# gdm-multiiface.net
KiCad netlist of a schematic drawn in EAGLE
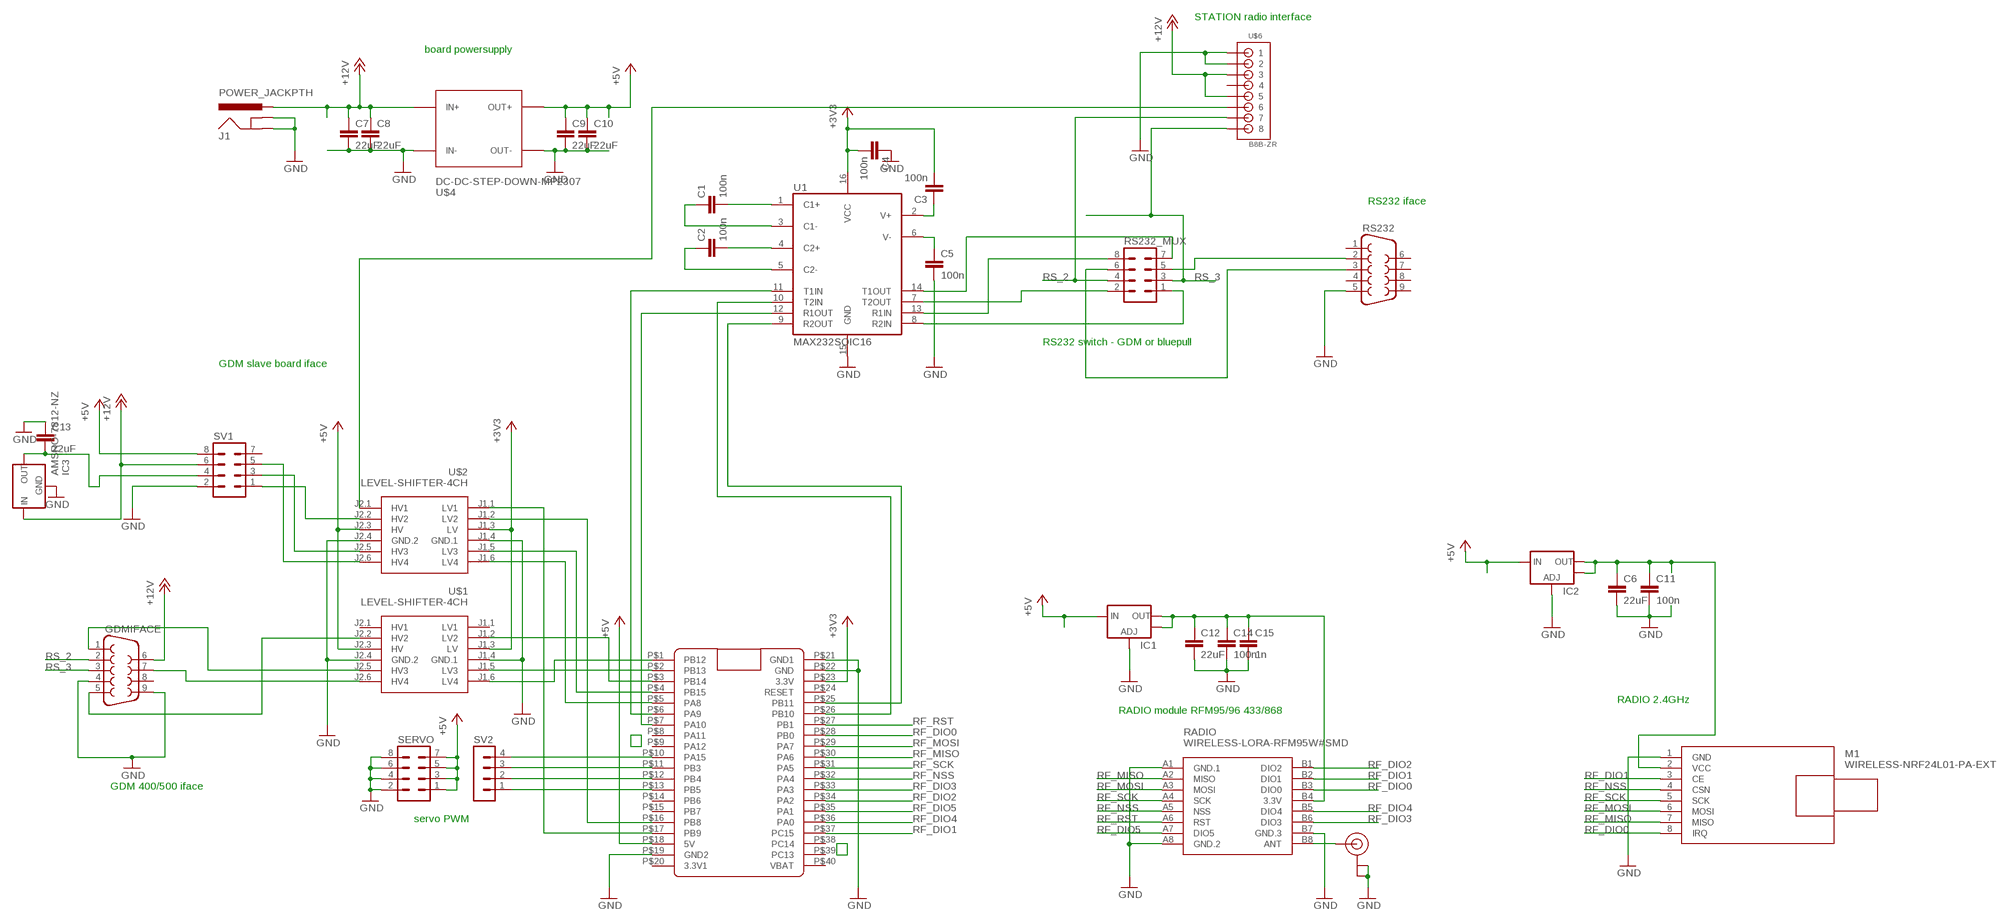
[diagram p0: schematic, sheet 1]

(export (version "E")
  (design (tool "Eeschema 10.0.6"))
  (components
    (comp (ref "BLUEPILL")
      (value "BLUE_PILL")
      (footprint "eagle-import:BLUE_PILL")
      (libsource (lib "eagle-import") (part "BLUE_PILL"))
    )
    (comp (ref "C1")
      (value "100n")
      (footprint "eagle-import:C0805")
      (libsource (lib "eagle-import") (part "C-EUC0805"))
    )
    (comp (ref "C2")
      (value "100n")
      (footprint "eagle-import:C0805")
      (libsource (lib "eagle-import") (part "C-EUC0805"))
    )
    (comp (ref "C3")
      (value "100n")
      (footprint "eagle-import:C0805")
      (libsource (lib "eagle-import") (part "C-EUC0805"))
    )
    (comp (ref "C4")
      (value "100n")
      (footprint "eagle-import:C0805")
      (libsource (lib "eagle-import") (part "C-EUC0805"))
    )
    (comp (ref "C5")
      (value "100n")
      (footprint "eagle-import:C0805")
      (libsource (lib "eagle-import") (part "C-EUC0805"))
    )
    (comp (ref "C6")
      (value "22uF")
      (footprint "eagle-import:C1210K")
      (libsource (lib "eagle-import") (part "C-EUC1210K"))
    )
    (comp (ref "C7")
      (value "22uF")
      (footprint "eagle-import:C1210K")
      (libsource (lib "eagle-import") (part "C-EUC1210K"))
    )
    (comp (ref "C8")
      (value "22uF")
      (footprint "eagle-import:C1210K")
      (libsource (lib "eagle-import") (part "C-EUC1210K"))
    )
    (comp (ref "C9")
      (value "22uF")
      (footprint "eagle-import:C1210K")
      (libsource (lib "eagle-import") (part "C-EUC1210K"))
    )
    (comp (ref "C10")
      (value "22uF")
      (footprint "eagle-import:C1210K")
      (libsource (lib "eagle-import") (part "C-EUC1210K"))
    )
    (comp (ref "C11")
      (value "100n")
      (footprint "eagle-import:C0805K")
      (libsource (lib "eagle-import") (part "C-EUC0805K"))
    )
    (comp (ref "C12")
      (value "22uF")
      (footprint "eagle-import:C1210K")
      (libsource (lib "eagle-import") (part "C-EUC1210K"))
    )
    (comp (ref "C13")
      (value "22uF")
      (footprint "eagle-import:C1210K")
      (libsource (lib "eagle-import") (part "C-EUC1210K"))
    )
    (comp (ref "C14")
      (value "100n")
      (footprint "eagle-import:C0805K")
      (libsource (lib "eagle-import") (part "C-EUC0805K"))
    )
    (comp (ref "C15")
      (value "1n")
      (footprint "eagle-import:C0805K")
      (libsource (lib "eagle-import") (part "C-EUC0805K"))
    )
    (comp (ref "GDMIFACE")
      (value "DB9FEMALE")
      (footprint "eagle-import:DB9")
      (libsource (lib "eagle-import") (part "DB9FEMALE"))
    )
    (comp (ref "IC1")
      (value "V_REG_LM1117SOT223")
      (footprint "eagle-import:SOT223")
      (libsource (lib "eagle-import") (part "V_REG_LM1117SOT223"))
    )
    (comp (ref "IC2")
      (value "V_REG_LM1117SOT223")
      (footprint "eagle-import:SOT223")
      (libsource (lib "eagle-import") (part "V_REG_LM1117SOT223"))
    )
    (comp (ref "IC3")
      (value "AMSRO-7812-NZ")
      (footprint "eagle-import:79XXS")
      (libsource (lib "eagle-import") (part "79XXS"))
    )
    (comp (ref "J1")
      (value "POWER_JACKPTH")
      (footprint "eagle-import:POWER_JACK_PTH")
      (libsource (lib "eagle-import") (part "POWER_JACKPTH"))
    )
    (comp (ref "M1")
      (value "WIRELESS-NRF24L01-PA-EXT")
      (footprint "eagle-import:WIRELESS-NRF24L01-PA-EXT")
      (libsource (lib "eagle-import") (part "WIRELESS-NRF24L01-PA-EXT"))
    )
    (comp (ref "RADIO")
      (value "WIRELESS-LORA-RFM95W#SMD")
      (footprint "eagle-import:WIRELESS-LORA-RFM95W#SMD")
      (libsource (lib "eagle-import") (part "WIRELESS-LORA-RFM95W#SMD"))
    )
    (comp (ref "RS232")
      (value "DB9FEMALE")
      (footprint "eagle-import:DB9")
      (libsource (lib "eagle-import") (part "DB9FEMALE"))
    )
    (comp (ref "RS232_MUX")
      (value "MA04-2")
      (footprint "eagle-import:MA04-2")
      (libsource (lib "eagle-import") (part "MA04-2"))
    )
    (comp (ref "SERVO")
      (value "MA04-2")
      (footprint "eagle-import:MA04-2")
      (libsource (lib "eagle-import") (part "MA04-2"))
    )
    (comp (ref "SV1")
      (value "MA04-2")
      (footprint "eagle-import:MA04-2")
      (libsource (lib "eagle-import") (part "MA04-2"))
    )
    (comp (ref "SV2")
      (value "MA04-1")
      (footprint "eagle-import:MA04-1")
      (libsource (lib "eagle-import") (part "MA04-1"))
    )
    (comp (ref "U$1")
      (value "LEVEL-SHIFTER-4CH")
      (footprint "eagle-import:LEVEL-SHIFTER-4CH")
      (libsource (lib "eagle-import") (part "LEVEL-SHIFTER-4CH"))
    )
    (comp (ref "U$2")
      (value "LEVEL-SHIFTER-4CH")
      (footprint "eagle-import:LEVEL-SHIFTER-4CH")
      (libsource (lib "eagle-import") (part "LEVEL-SHIFTER-4CH"))
    )
    (comp (ref "U$3")
      (value "U.FL")
      (footprint "eagle-import:U.FL")
      (libsource (lib "eagle-import") (part "U.FL"))
    )
    (comp (ref "U$4")
      (value "DC-DC-STEP-DOWN-MP2307")
      (footprint "eagle-import:DC-DC-STEP-DOWN-MP2307")
      (libsource (lib "eagle-import") (part "DC-DC-STEP-DOWN-MP2307"))
    )
    (comp (ref "U$6")
      (value "B8B-ZR")
      (footprint "eagle-import:B8B-ZR")
      (libsource (lib "eagle-import") (part "B8B-ZR"))
    )
    (comp (ref "U1")
      (value "MAX232SOIC16")
      (footprint "eagle-import:SO016")
      (libsource (lib "eagle-import") (part "MAX232SOIC16"))
    )
  )
  (nets
    (net (code "1") (name "+3V3") (class "Default")
      (node (ref "BLUEPILL") (pin "P$23") (pinfunction "3.3V_P$23") (pintype "bidirectional"))
      (node (ref "C3") (pin "2") (pinfunction "2_2") (pintype "passive"))
      (node (ref "C4") (pin "2") (pinfunction "2_2") (pintype "passive"))
      (node (ref "U$1") (pin "J1.3") (pinfunction "LV_J1.3") (pintype "power_in"))
      (node (ref "U$2") (pin "J1.3") (pinfunction "LV_J1.3") (pintype "power_in"))
      (node (ref "U1") (pin "16") (pinfunction "VCC_16") (pintype "bidirectional"))
    )
    (net (code "2") (name "+5V") (class "Default")
      (node (ref "BLUEPILL") (pin "P$18") (pinfunction "5V_P$18") (pintype "bidirectional"))
      (node (ref "C10") (pin "1") (pinfunction "1_1") (pintype "passive"))
      (node (ref "C9") (pin "1") (pinfunction "1_1") (pintype "passive"))
      (node (ref "IC1") (pin "3") (pinfunction "IN_3") (pintype "input"))
      (node (ref "IC2") (pin "3") (pinfunction "IN_3") (pintype "input"))
      (node (ref "SERVO") (pin "1") (pinfunction "1_1") (pintype "passive"))
      (node (ref "SERVO") (pin "3") (pinfunction "3_3") (pintype "passive"))
      (node (ref "SERVO") (pin "5") (pinfunction "5_5") (pintype "passive"))
      (node (ref "SERVO") (pin "7") (pinfunction "7_7") (pintype "passive"))
      (node (ref "SV1") (pin "8") (pinfunction "8_8") (pintype "passive"))
      (node (ref "U$1") (pin "J2.3") (pinfunction "HV_J2.3") (pintype "power_in"))
      (node (ref "U$2") (pin "J2.3") (pinfunction "HV_J2.3") (pintype "power_in"))
      (node (ref "U$4") (pin "OUT+") (pinfunction "OUT+_OUT+") (pintype "bidirectional"))
    )
    (net (code "3") (name "+12V") (class "Default")
      (node (ref "C7") (pin "1") (pinfunction "1_1") (pintype "passive"))
      (node (ref "C8") (pin "1") (pinfunction "1_1") (pintype "passive"))
      (node (ref "GDMIFACE") (pin "6") (pinfunction "6_6") (pintype "passive"))
      (node (ref "IC3") (pin "IN") (pinfunction "IN_IN") (pintype "input"))
      (node (ref "J1") (pin "PWR") (pinfunction "PWR_PWR") (pintype "bidirectional"))
      (node (ref "SV1") (pin "6") (pinfunction "6_6") (pintype "passive"))
      (node (ref "U$4") (pin "IN+") (pinfunction "IN+_IN+") (pintype "bidirectional"))
      (node (ref "U$6") (pin "3") (pinfunction "3_3") (pintype "bidirectional"))
      (node (ref "U$6") (pin "5") (pinfunction "5_5") (pintype "bidirectional"))
    )
    (net (code "4") (name "/RF_DIO0") (class "Default")
      (node (ref "BLUEPILL") (pin "P$28") (pinfunction "PB0_P$28") (pintype "bidirectional"))
      (node (ref "M1") (pin "8") (pinfunction "IRQ_8") (pintype "bidirectional"))
      (node (ref "RADIO") (pin "B3") (pinfunction "DIO0_B3") (pintype "bidirectional"))
    )
    (net (code "5") (name "/RF_DIO1") (class "Default")
      (node (ref "BLUEPILL") (pin "P$37") (pinfunction "PC15_P$37") (pintype "bidirectional"))
      (node (ref "M1") (pin "3") (pinfunction "CE_3") (pintype "bidirectional"))
      (node (ref "RADIO") (pin "B2") (pinfunction "DIO1_B2") (pintype "bidirectional"))
    )
    (net (code "6") (name "/RF_DIO2") (class "Default")
      (node (ref "BLUEPILL") (pin "P$34") (pinfunction "PA2_P$34") (pintype "bidirectional"))
      (node (ref "RADIO") (pin "B1") (pinfunction "DIO2_B1") (pintype "bidirectional"))
    )
    (net (code "7") (name "/RF_DIO3") (class "Default")
      (node (ref "BLUEPILL") (pin "P$33") (pinfunction "PA3_P$33") (pintype "bidirectional"))
      (node (ref "RADIO") (pin "B6") (pinfunction "DIO3_B6") (pintype "bidirectional"))
    )
    (net (code "8") (name "/RF_DIO4") (class "Default")
      (node (ref "BLUEPILL") (pin "P$36") (pinfunction "PA0_P$36") (pintype "bidirectional"))
      (node (ref "RADIO") (pin "B5") (pinfunction "DIO4_B5") (pintype "bidirectional"))
    )
    (net (code "9") (name "/RF_DIO5") (class "Default")
      (node (ref "BLUEPILL") (pin "P$35") (pinfunction "PA1_P$35") (pintype "bidirectional"))
      (node (ref "RADIO") (pin "A7") (pinfunction "DIO5_A7") (pintype "bidirectional"))
    )
    (net (code "10") (name "/RF_MISO") (class "Default")
      (node (ref "BLUEPILL") (pin "P$30") (pinfunction "PA6_P$30") (pintype "bidirectional"))
      (node (ref "M1") (pin "7") (pinfunction "MISO_7") (pintype "bidirectional"))
      (node (ref "RADIO") (pin "A2") (pinfunction "MISO_A2") (pintype "bidirectional"))
    )
    (net (code "11") (name "/RF_MOSI") (class "Default")
      (node (ref "BLUEPILL") (pin "P$29") (pinfunction "PA7_P$29") (pintype "bidirectional"))
      (node (ref "M1") (pin "6") (pinfunction "MOSI_6") (pintype "bidirectional"))
      (node (ref "RADIO") (pin "A3") (pinfunction "MOSI_A3") (pintype "bidirectional"))
    )
    (net (code "12") (name "/RF_NSS") (class "Default")
      (node (ref "BLUEPILL") (pin "P$32") (pinfunction "PA4_P$32") (pintype "bidirectional"))
      (node (ref "M1") (pin "4") (pinfunction "CSN_4") (pintype "bidirectional"))
      (node (ref "RADIO") (pin "A5") (pinfunction "NSS_A5") (pintype "bidirectional"))
    )
    (net (code "13") (name "/RF_RST") (class "Default")
      (node (ref "BLUEPILL") (pin "P$27") (pinfunction "PB1_P$27") (pintype "bidirectional"))
      (node (ref "RADIO") (pin "A6") (pinfunction "RST_A6") (pintype "bidirectional"))
    )
    (net (code "14") (name "/RF_SCK") (class "Default")
      (node (ref "BLUEPILL") (pin "P$31") (pinfunction "PA5_P$31") (pintype "bidirectional"))
      (node (ref "M1") (pin "5") (pinfunction "SCK_5") (pintype "bidirectional"))
      (node (ref "RADIO") (pin "A4") (pinfunction "SCK_A4") (pintype "bidirectional"))
    )
    (net (code "15") (name "/RS_2") (class "Default")
      (node (ref "GDMIFACE") (pin "2") (pinfunction "2_2") (pintype "passive"))
      (node (ref "RS232_MUX") (pin "4") (pinfunction "4_4") (pintype "passive"))
      (node (ref "U$6") (pin "7") (pinfunction "7_7") (pintype "bidirectional"))
    )
    (net (code "16") (name "/RS_3") (class "Default")
      (node (ref "GDMIFACE") (pin "3") (pinfunction "3_3") (pintype "passive"))
      (node (ref "RS232_MUX") (pin "3") (pinfunction "3_3") (pintype "passive"))
      (node (ref "U$6") (pin "8") (pinfunction "8_8") (pintype "bidirectional"))
    )
    (net (code "17") (name "GND") (class "Default")
      (node (ref "BLUEPILL") (pin "P$19") (pinfunction "GND2_P$19") (pintype "bidirectional"))
      (node (ref "BLUEPILL") (pin "P$21") (pinfunction "GND1_P$21") (pintype "power_in"))
      (node (ref "BLUEPILL") (pin "P$22") (pinfunction "GND_P$22") (pintype "bidirectional"))
      (node (ref "C10") (pin "2") (pinfunction "2_2") (pintype "passive"))
      (node (ref "C11") (pin "2") (pinfunction "2_2") (pintype "passive"))
      (node (ref "C12") (pin "2") (pinfunction "2_2") (pintype "passive"))
      (node (ref "C13") (pin "1") (pinfunction "1_1") (pintype "passive"))
      (node (ref "C14") (pin "2") (pinfunction "2_2") (pintype "passive"))
      (node (ref "C15") (pin "2") (pinfunction "2_2") (pintype "passive"))
      (node (ref "C4") (pin "1") (pinfunction "1_1") (pintype "passive"))
      (node (ref "C5") (pin "2") (pinfunction "2_2") (pintype "passive"))
      (node (ref "C6") (pin "2") (pinfunction "2_2") (pintype "passive"))
      (node (ref "C7") (pin "2") (pinfunction "2_2") (pintype "passive"))
      (node (ref "C8") (pin "2") (pinfunction "2_2") (pintype "passive"))
      (node (ref "C9") (pin "2") (pinfunction "2_2") (pintype "passive"))
      (node (ref "GDMIFACE") (pin "4") (pinfunction "4_4") (pintype "passive"))
      (node (ref "GDMIFACE") (pin "9") (pinfunction "9_9") (pintype "passive"))
      (node (ref "IC1") (pin "1") (pinfunction "ADJ_1") (pintype "input"))
      (node (ref "IC2") (pin "1") (pinfunction "ADJ_1") (pintype "input"))
      (node (ref "IC3") (pin "GND") (pinfunction "GND_GND") (pintype "input"))
      (node (ref "J1") (pin "GND") (pinfunction "GND_GND") (pintype "bidirectional"))
      (node (ref "J1") (pin "GNDBREAK") (pinfunction "GNDBREAK_GNDBREAK") (pintype "bidirectional"))
      (node (ref "M1") (pin "1") (pinfunction "GND_1") (pintype "power_in"))
      (node (ref "RADIO") (pin "A1") (pinfunction "GND.1_A1") (pintype "power_in"))
      (node (ref "RADIO") (pin "A8") (pinfunction "GND.2_A8") (pintype "power_in"))
      (node (ref "RADIO") (pin "B7") (pinfunction "GND.3_B7") (pintype "power_in"))
      (node (ref "RS232") (pin "5") (pinfunction "5_5") (pintype "passive"))
      (node (ref "SERVO") (pin "2") (pinfunction "2_2") (pintype "passive"))
      (node (ref "SERVO") (pin "4") (pinfunction "4_4") (pintype "passive"))
      (node (ref "SERVO") (pin "6") (pinfunction "6_6") (pintype "passive"))
      (node (ref "SERVO") (pin "8") (pinfunction "8_8") (pintype "passive"))
      (node (ref "SV1") (pin "2") (pinfunction "2_2") (pintype "passive"))
      (node (ref "U$1") (pin "J1.4") (pinfunction "GND.1_J1.4") (pintype "power_in"))
      (node (ref "U$1") (pin "J2.4") (pinfunction "GND.2_J2.4") (pintype "power_in"))
      (node (ref "U$2") (pin "J1.4") (pinfunction "GND.1_J1.4") (pintype "power_in"))
      (node (ref "U$2") (pin "J2.4") (pinfunction "GND.2_J2.4") (pintype "power_in"))
      (node (ref "U$3") (pin "P$1") (pinfunction "GND_P$1") (pintype "bidirectional"))
      (node (ref "U$3") (pin "P$2") (pinfunction "GND_P$2") (pintype "bidirectional"))
      (node (ref "U$4") (pin "IN-") (pinfunction "IN-_IN-") (pintype "bidirectional"))
      (node (ref "U$4") (pin "OUT-") (pinfunction "OUT-_OUT-") (pintype "bidirectional"))
      (node (ref "U$6") (pin "1") (pinfunction "1_1") (pintype "bidirectional"))
      (node (ref "U$6") (pin "2") (pinfunction "2_2") (pintype "bidirectional"))
      (node (ref "U1") (pin "15") (pinfunction "GND_15") (pintype "bidirectional"))
    )
    (net (code "18") (name "Net-(BLUEPILL-PA8)") (class "Default")
      (node (ref "BLUEPILL") (pin "P$5") (pinfunction "PA8_P$5") (pintype "bidirectional"))
      (node (ref "U$2") (pin "J1.6") (pinfunction "LV4_J1.6") (pintype "bidirectional"))
    )
    (net (code "19") (name "Net-(BLUEPILL-PA9)") (class "Default")
      (node (ref "BLUEPILL") (pin "P$6") (pinfunction "PA9_P$6") (pintype "bidirectional"))
      (node (ref "U1") (pin "11") (pinfunction "T1IN_11") (pintype "input"))
    )
    (net (code "20") (name "Net-(BLUEPILL-PA10)") (class "Default")
      (node (ref "BLUEPILL") (pin "P$7") (pinfunction "PA10_P$7") (pintype "bidirectional"))
      (node (ref "U1") (pin "12") (pinfunction "R1OUT_12") (pintype "output"))
    )
    (net (code "21") (name "Net-(BLUEPILL-PA15)") (class "Default")
      (node (ref "BLUEPILL") (pin "P$10") (pinfunction "PA15_P$10") (pintype "bidirectional"))
      (node (ref "SV2") (pin "4") (pinfunction "4_4") (pintype "passive"))
    )
    (net (code "22") (name "Net-(BLUEPILL-PB3)") (class "Default")
      (node (ref "BLUEPILL") (pin "P$11") (pinfunction "PB3_P$11") (pintype "bidirectional"))
      (node (ref "SV2") (pin "3") (pinfunction "3_3") (pintype "passive"))
    )
    (net (code "23") (name "Net-(BLUEPILL-PB4)") (class "Default")
      (node (ref "BLUEPILL") (pin "P$12") (pinfunction "PB4_P$12") (pintype "bidirectional"))
      (node (ref "SV2") (pin "2") (pinfunction "2_2") (pintype "passive"))
    )
    (net (code "24") (name "Net-(BLUEPILL-PB5)") (class "Default")
      (node (ref "BLUEPILL") (pin "P$13") (pinfunction "PB5_P$13") (pintype "bidirectional"))
      (node (ref "SV2") (pin "1") (pinfunction "1_1") (pintype "passive"))
    )
    (net (code "25") (name "Net-(BLUEPILL-PB8)") (class "Default")
      (node (ref "BLUEPILL") (pin "P$16") (pinfunction "PB8_P$16") (pintype "bidirectional"))
      (node (ref "U$2") (pin "J1.2") (pinfunction "LV2_J1.2") (pintype "bidirectional"))
    )
    (net (code "26") (name "Net-(BLUEPILL-PB9)") (class "Default")
      (node (ref "BLUEPILL") (pin "P$17") (pinfunction "PB9_P$17") (pintype "bidirectional"))
      (node (ref "U$2") (pin "J1.1") (pinfunction "LV1_J1.1") (pintype "bidirectional"))
    )
    (net (code "27") (name "Net-(BLUEPILL-PB10)") (class "Default")
      (node (ref "BLUEPILL") (pin "P$26") (pinfunction "PB10_P$26") (pintype "bidirectional"))
      (node (ref "U1") (pin "10") (pinfunction "T2IN_10") (pintype "input"))
    )
    (net (code "28") (name "Net-(BLUEPILL-PB11)") (class "Default")
      (node (ref "BLUEPILL") (pin "P$25") (pinfunction "PB11_P$25") (pintype "bidirectional"))
      (node (ref "U1") (pin "9") (pinfunction "R2OUT_9") (pintype "output"))
    )
    (net (code "29") (name "Net-(BLUEPILL-PB12)") (class "Default")
      (node (ref "BLUEPILL") (pin "P$1") (pinfunction "PB12_P$1") (pintype "bidirectional"))
      (node (ref "U$1") (pin "J1.6") (pinfunction "LV4_J1.6") (pintype "bidirectional"))
    )
    (net (code "30") (name "Net-(BLUEPILL-PB13)") (class "Default")
      (node (ref "BLUEPILL") (pin "P$2") (pinfunction "PB13_P$2") (pintype "bidirectional"))
      (node (ref "U$1") (pin "J1.5") (pinfunction "LV3_J1.5") (pintype "bidirectional"))
    )
    (net (code "31") (name "Net-(BLUEPILL-PB14)") (class "Default")
      (node (ref "BLUEPILL") (pin "P$3") (pinfunction "PB14_P$3") (pintype "bidirectional"))
      (node (ref "U$1") (pin "J1.2") (pinfunction "LV2_J1.2") (pintype "bidirectional"))
    )
    (net (code "32") (name "Net-(BLUEPILL-PB15)") (class "Default")
      (node (ref "BLUEPILL") (pin "P$4") (pinfunction "PB15_P$4") (pintype "bidirectional"))
      (node (ref "U$2") (pin "J1.5") (pinfunction "LV3_J1.5") (pintype "bidirectional"))
    )
    (net (code "33") (name "Net-(C13-Pad2)") (class "Default")
      (node (ref "C13") (pin "2") (pinfunction "2_2") (pintype "passive"))
      (node (ref "IC3") (pin "OUT") (pinfunction "OUT_OUT") (pintype "passive"))
      (node (ref "SV1") (pin "4") (pinfunction "4_4") (pintype "passive"))
    )
    (net (code "34") (name "Net-(M1-VCC)") (class "Default")
      (node (ref "C11") (pin "1") (pinfunction "1_1") (pintype "passive"))
      (node (ref "C6") (pin "1") (pinfunction "1_1") (pintype "passive"))
      (node (ref "IC2") (pin "2") (pinfunction "OUT_2") (pintype "output"))
      (node (ref "IC2") (pin "4") (pinfunction "OUT_4") (pintype "output"))
      (node (ref "M1") (pin "2") (pinfunction "VCC_2") (pintype "power_in"))
    )
    (net (code "35") (name "Net-(RADIO-3.3V)") (class "Default")
      (node (ref "C12") (pin "1") (pinfunction "1_1") (pintype "passive"))
      (node (ref "C14") (pin "1") (pinfunction "1_1") (pintype "passive"))
      (node (ref "C15") (pin "1") (pinfunction "1_1") (pintype "passive"))
      (node (ref "IC1") (pin "2") (pinfunction "OUT_2") (pintype "output"))
      (node (ref "IC1") (pin "4") (pinfunction "OUT_4") (pintype "output"))
      (node (ref "RADIO") (pin "B4") (pinfunction "3.3V_B4") (pintype "power_in"))
    )
    (net (code "36") (name "Net-(RADIO-ANT)") (class "Default")
      (node (ref "RADIO") (pin "B8") (pinfunction "ANT_B8") (pintype "passive"))
      (node (ref "U$3") (pin "P$3") (pinfunction "SIGNAL_P$3") (pintype "bidirectional"))
    )
    (net (code "37") (name "Net-(RS232-Pad2)") (class "Default")
      (node (ref "RS232") (pin "2") (pinfunction "2_2") (pintype "passive"))
      (node (ref "RS232_MUX") (pin "5") (pinfunction "5_5") (pintype "passive"))
    )
    (net (code "38") (name "Net-(RS232-Pad3)") (class "Default")
      (node (ref "RS232") (pin "3") (pinfunction "3_3") (pintype "passive"))
      (node (ref "RS232_MUX") (pin "6") (pinfunction "6_6") (pintype "passive"))
    )
    (net (code "39") (name "Net-(U$1-HV2)") (class "Default")
      (node (ref "GDMIFACE") (pin "5") (pinfunction "5_5") (pintype "passive"))
      (node (ref "U$1") (pin "J2.2") (pinfunction "HV2_J2.2") (pintype "bidirectional"))
    )
    (net (code "40") (name "Net-(U$1-HV3)") (class "Default")
      (node (ref "GDMIFACE") (pin "1") (pinfunction "1_1") (pintype "passive"))
      (node (ref "U$1") (pin "J2.5") (pinfunction "HV3_J2.5") (pintype "bidirectional"))
    )
    (net (code "41") (name "Net-(U$1-HV4)") (class "Default")
      (node (ref "GDMIFACE") (pin "7") (pinfunction "7_7") (pintype "passive"))
      (node (ref "U$1") (pin "J2.6") (pinfunction "HV4_J2.6") (pintype "bidirectional"))
    )
    (net (code "42") (name "Net-(U$2-HV1)") (class "Default")
      (node (ref "U$2") (pin "J2.1") (pinfunction "HV1_J2.1") (pintype "bidirectional"))
      (node (ref "U$6") (pin "6") (pinfunction "6_6") (pintype "bidirectional"))
    )
    (net (code "43") (name "Net-(U$2-HV2)") (class "Default")
      (node (ref "SV1") (pin "1") (pinfunction "1_1") (pintype "passive"))
      (node (ref "U$2") (pin "J2.2") (pinfunction "HV2_J2.2") (pintype "bidirectional"))
    )
    (net (code "44") (name "Net-(U$2-HV3)") (class "Default")
      (node (ref "SV1") (pin "3") (pinfunction "3_3") (pintype "passive"))
      (node (ref "U$2") (pin "J2.5") (pinfunction "HV3_J2.5") (pintype "bidirectional"))
    )
    (net (code "45") (name "Net-(U$2-HV4)") (class "Default")
      (node (ref "SV1") (pin "5") (pinfunction "5_5") (pintype "passive"))
      (node (ref "U$2") (pin "J2.6") (pinfunction "HV4_J2.6") (pintype "bidirectional"))
    )
    (net (code "46") (name "Net-(U1-C1+)") (class "Default")
      (node (ref "C1") (pin "2") (pinfunction "2_2") (pintype "passive"))
      (node (ref "U1") (pin "1") (pinfunction "C1+_1") (pintype "bidirectional"))
    )
    (net (code "47") (name "Net-(U1-C1-)") (class "Default")
      (node (ref "C1") (pin "1") (pinfunction "1_1") (pintype "passive"))
      (node (ref "U1") (pin "3") (pinfunction "C1-_3") (pintype "bidirectional"))
    )
    (net (code "48") (name "Net-(U1-C2+)") (class "Default")
      (node (ref "C2") (pin "2") (pinfunction "2_2") (pintype "passive"))
      (node (ref "U1") (pin "4") (pinfunction "C2+_4") (pintype "bidirectional"))
    )
    (net (code "49") (name "Net-(U1-C2-)") (class "Default")
      (node (ref "C2") (pin "1") (pinfunction "1_1") (pintype "passive"))
      (node (ref "U1") (pin "5") (pinfunction "C2-_5") (pintype "bidirectional"))
    )
    (net (code "50") (name "Net-(U1-R1IN)") (class "Default")
      (node (ref "RS232_MUX") (pin "8") (pinfunction "8_8") (pintype "passive"))
      (node (ref "U1") (pin "13") (pinfunction "R1IN_13") (pintype "input"))
    )
    (net (code "51") (name "Net-(U1-R2IN)") (class "Default")
      (node (ref "RS232_MUX") (pin "1") (pinfunction "1_1") (pintype "passive"))
      (node (ref "U1") (pin "8") (pinfunction "R2IN_8") (pintype "input"))
    )
    (net (code "52") (name "Net-(U1-T1OUT)") (class "Default")
      (node (ref "RS232_MUX") (pin "7") (pinfunction "7_7") (pintype "passive"))
      (node (ref "U1") (pin "14") (pinfunction "T1OUT_14") (pintype "output"))
    )
    (net (code "53") (name "Net-(U1-T2OUT)") (class "Default")
      (node (ref "RS232_MUX") (pin "2") (pinfunction "2_2") (pintype "passive"))
      (node (ref "U1") (pin "7") (pinfunction "T2OUT_7") (pintype "output"))
    )
    (net (code "54") (name "Net-(U1-V+)") (class "Default")
      (node (ref "C3") (pin "1") (pinfunction "1_1") (pintype "passive"))
      (node (ref "U1") (pin "2") (pinfunction "V+_2") (pintype "bidirectional"))
    )
    (net (code "55") (name "Net-(U1-V-)") (class "Default")
      (node (ref "C5") (pin "1") (pinfunction "1_1") (pintype "passive"))
      (node (ref "U1") (pin "6") (pinfunction "V-_6") (pintype "bidirectional"))
    )
    (net (code "56") (name "unconnected-(BLUEPILL-3.3V1-PadP$20)") (class "Default")
      (node (ref "BLUEPILL") (pin "P$20") (pinfunction "3.3V1_P$20") (pintype "bidirectional"))
    )
    (net (code "57") (name "unconnected-(BLUEPILL-PA11-PadP$8)") (class "Default")
      (node (ref "BLUEPILL") (pin "P$8") (pinfunction "PA11_P$8") (pintype "bidirectional"))
    )
    (net (code "58") (name "unconnected-(BLUEPILL-PA12-PadP$9)") (class "Default")
      (node (ref "BLUEPILL") (pin "P$9") (pinfunction "PA12_P$9") (pintype "bidirectional"))
    )
    (net (code "59") (name "unconnected-(BLUEPILL-PB6-PadP$14)") (class "Default")
      (node (ref "BLUEPILL") (pin "P$14") (pinfunction "PB6_P$14") (pintype "bidirectional"))
    )
    (net (code "60") (name "unconnected-(BLUEPILL-PB7-PadP$15)") (class "Default")
      (node (ref "BLUEPILL") (pin "P$15") (pinfunction "PB7_P$15") (pintype "bidirectional"))
    )
    (net (code "61") (name "unconnected-(BLUEPILL-PC13-PadP$39)") (class "Default")
      (node (ref "BLUEPILL") (pin "P$39") (pinfunction "PC13_P$39") (pintype "bidirectional"))
    )
    (net (code "62") (name "unconnected-(BLUEPILL-PC14-PadP$38)") (class "Default")
      (node (ref "BLUEPILL") (pin "P$38") (pinfunction "PC14_P$38") (pintype "bidirectional"))
    )
    (net (code "63") (name "unconnected-(BLUEPILL-RESET-PadP$24)") (class "Default")
      (node (ref "BLUEPILL") (pin "P$24") (pinfunction "RESET_P$24") (pintype "bidirectional"))
    )
    (net (code "64") (name "unconnected-(BLUEPILL-VBAT-PadP$40)") (class "Default")
      (node (ref "BLUEPILL") (pin "P$40") (pinfunction "VBAT_P$40") (pintype "bidirectional"))
    )
    (net (code "65") (name "unconnected-(GDMIFACE-Pad8)") (class "Default")
      (node (ref "GDMIFACE") (pin "8") (pinfunction "8_8") (pintype "passive"))
    )
    (net (code "66") (name "unconnected-(RS232-Pad1)") (class "Default")
      (node (ref "RS232") (pin "1") (pinfunction "1_1") (pintype "passive"))
    )
    (net (code "67") (name "unconnected-(RS232-Pad4)") (class "Default")
      (node (ref "RS232") (pin "4") (pinfunction "4_4") (pintype "passive"))
    )
    (net (code "68") (name "unconnected-(RS232-Pad6)") (class "Default")
      (node (ref "RS232") (pin "6") (pinfunction "6_6") (pintype "passive"))
    )
    (net (code "69") (name "unconnected-(RS232-Pad7)") (class "Default")
      (node (ref "RS232") (pin "7") (pinfunction "7_7") (pintype "passive"))
    )
    (net (code "70") (name "unconnected-(RS232-Pad8)") (class "Default")
      (node (ref "RS232") (pin "8") (pinfunction "8_8") (pintype "passive"))
    )
    (net (code "71") (name "unconnected-(RS232-Pad9)") (class "Default")
      (node (ref "RS232") (pin "9") (pinfunction "9_9") (pintype "passive"))
    )
    (net (code "72") (name "unconnected-(SV1-Pad7)") (class "Default")
      (node (ref "SV1") (pin "7") (pinfunction "7_7") (pintype "passive"))
    )
    (net (code "73") (name "unconnected-(U$1-HV1-PadJ2.1)") (class "Default")
      (node (ref "U$1") (pin "J2.1") (pinfunction "HV1_J2.1") (pintype "bidirectional"))
    )
    (net (code "74") (name "unconnected-(U$1-LV1-PadJ1.1)") (class "Default")
      (node (ref "U$1") (pin "J1.1") (pinfunction "LV1_J1.1") (pintype "bidirectional"))
    )
    (net (code "75") (name "unconnected-(U$6-Pad4)") (class "Default")
      (node (ref "U$6") (pin "4") (pinfunction "4_4") (pintype "bidirectional"))
    )
  )
)
